# 1-Schematic_barbot_version1.net
KiCad netlist of a schematic drawn in EasyEDA
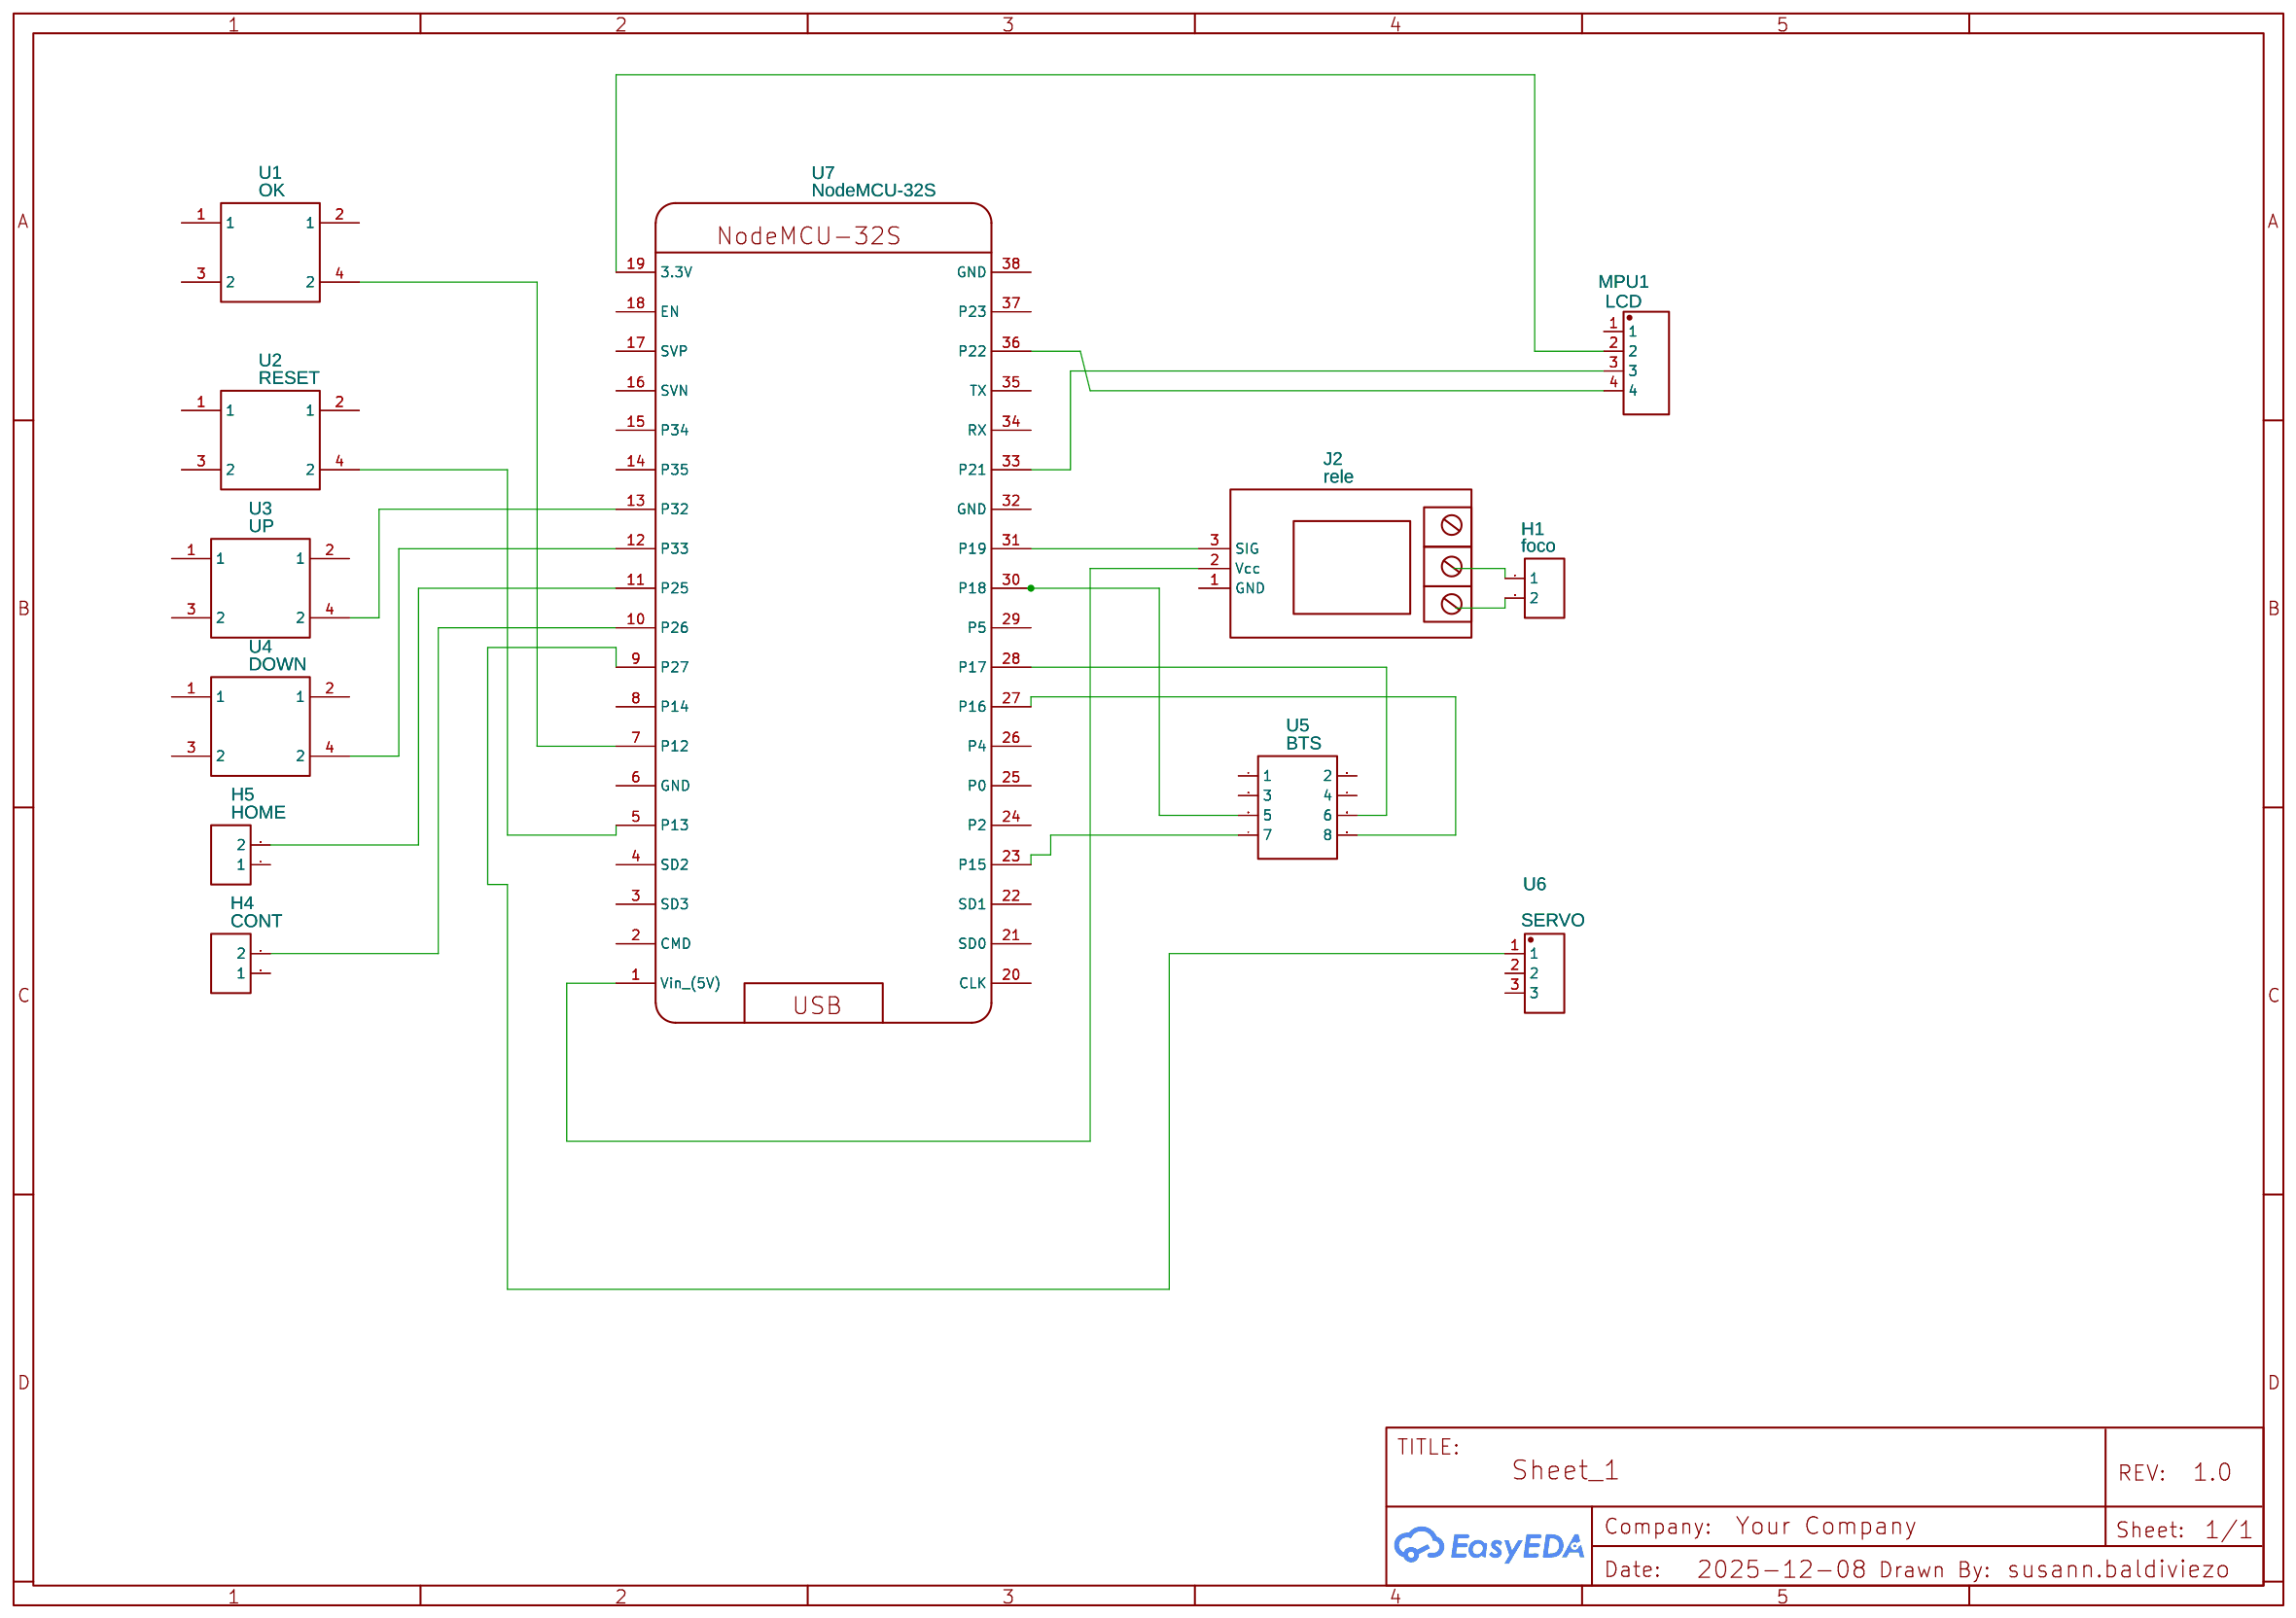
[diagram p0: schematic sheet]

(export (version "E")
  (design (tool "Eeschema 10.0.6"))
  (components
    (comp (ref "H1") (value "foco") (libsource (lib "") (part "HEADER-FEMALE-2.54_1X2 COPY")))
    (comp (ref "H4") (value "CONT") (libsource (lib "") (part "HEADER-FEMALE-2.54_1X2 COPY_1")))
    (comp (ref "H5") (value "HOME") (libsource (lib "") (part "HEADER-FEMALE-2.54_1X2 COPY_1")))
    (comp (ref "J2")
      (value "rele")
      (fields (field (name "Manufacturer Part") "1-Channel 5V Relay Module w/ Opto-isolator"))
      (libsource (lib "") (part "1 CHANNEL RELAY MODULE"))
    )
    (comp (ref "MPU1") (value "LCD") (libsource (lib "") (part "HEADER-FEMALE-2.54_1X4")))
    (comp (ref "U1") (value "OK") (libsource (lib "") (part "Boton pulsador 12x12mm")))
    (comp (ref "U2") (value "RESET") (libsource (lib "") (part "Boton pulsador 12x12mm")))
    (comp (ref "U3") (value "UP") (libsource (lib "") (part "Boton pulsador 12x12mm")))
    (comp (ref "U4") (value "DOWN") (libsource (lib "") (part "Boton pulsador 12x12mm")))
    (comp (ref "U5")
      (value "BTS")
      (fields (field (name "Manufacturer Part") "2.54mm,2×4Double row female"))
      (libsource (lib "") (part "Header-Female-2.54_2x10"))
    )
    (comp (ref "U6") (value "SERVO") (libsource (lib "") (part "HEADER-FEMALE-2.54_1X3")))
    (comp (ref "U7")
      (value "NodeMCU-32S")
      (fields (field (name "Manufacturer Part") "NodeMCU-32SLua") (field (name "Manufacturer") "Ai-Thinker"))
      (libsource (lib "") (part "NodeMCU-32S"))
    )
  )
  (nets
    (net (code "1") (name "Net-(J2-SIG)") (class "Default")
      (node (ref "J2") (pin "3") (pinfunction "SIG_3") (pintype "input"))
      (node (ref "U7") (pin "31") (pinfunction "P19_31") (pintype "unspecified"))
    )
    (net (code "2") (name "Net-(J2-Vcc)") (class "Default")
      (node (ref "J2") (pin "2") (pinfunction "Vcc_2") (pintype "input"))
      (node (ref "U7") (pin "1") (pinfunction "Vin_(5V)_1") (pintype "unspecified"))
    )
    (net (code "3") (name "Net-(U7-3.3V)") (class "Default")
      (node (ref "MPU1") (pin "2") (pinfunction "2_2") (pintype "unspecified"))
      (node (ref "U7") (pin "19") (pinfunction "3.3V_19") (pintype "unspecified"))
    )
    (net (code "4") (name "Net-(U7-P12)") (class "Default")
      (node (ref "U1") (pin "4") (pinfunction "2_4") (pintype "unspecified"))
      (node (ref "U7") (pin "7") (pinfunction "P12_7") (pintype "unspecified"))
    )
    (net (code "5") (name "Net-(U7-P13)") (class "Default")
      (node (ref "U2") (pin "4") (pinfunction "2_4") (pintype "unspecified"))
      (node (ref "U7") (pin "5") (pinfunction "P13_5") (pintype "unspecified"))
    )
    (net (code "6") (name "Net-(U7-P15)") (class "Default")
      (node (ref "U5") (pin "7") (pinfunction "7_7") (pintype "unspecified"))
      (node (ref "U7") (pin "23") (pinfunction "P15_23") (pintype "unspecified"))
    )
    (net (code "7") (name "Net-(U7-P16)") (class "Default")
      (node (ref "U5") (pin "8") (pinfunction "8_8") (pintype "unspecified"))
      (node (ref "U7") (pin "27") (pinfunction "P16_27") (pintype "unspecified"))
    )
    (net (code "8") (name "Net-(U7-P17)") (class "Default")
      (node (ref "U5") (pin "6") (pinfunction "6_6") (pintype "unspecified"))
      (node (ref "U7") (pin "28") (pinfunction "P17_28") (pintype "unspecified"))
    )
    (net (code "9") (name "Net-(U7-P18)") (class "Default")
      (node (ref "U5") (pin "5") (pinfunction "5_5") (pintype "unspecified"))
      (node (ref "U7") (pin "30") (pinfunction "P18_30") (pintype "unspecified"))
    )
    (net (code "10") (name "Net-(U7-P21)") (class "Default")
      (node (ref "MPU1") (pin "3") (pinfunction "3_3") (pintype "unspecified"))
      (node (ref "U7") (pin "33") (pinfunction "P21_33") (pintype "unspecified"))
    )
    (net (code "11") (name "Net-(U7-P22)") (class "Default")
      (node (ref "MPU1") (pin "4") (pinfunction "4_4") (pintype "unspecified"))
      (node (ref "U7") (pin "36") (pinfunction "P22_36") (pintype "unspecified"))
    )
    (net (code "12") (name "Net-(U7-P25)") (class "Default")
      (node (ref "H5") (pin "2") (pinfunction "2_2") (pintype "input"))
      (node (ref "U7") (pin "11") (pinfunction "P25_11") (pintype "unspecified"))
    )
    (net (code "13") (name "Net-(U7-P26)") (class "Default")
      (node (ref "H4") (pin "2") (pinfunction "2_2") (pintype "input"))
      (node (ref "U7") (pin "10") (pinfunction "P26_10") (pintype "unspecified"))
    )
    (net (code "14") (name "Net-(U7-P27)") (class "Default")
      (node (ref "U6") (pin "1") (pinfunction "1_1") (pintype "unspecified"))
      (node (ref "U7") (pin "9") (pinfunction "P27_9") (pintype "unspecified"))
    )
    (net (code "15") (name "Net-(U7-P32)") (class "Default")
      (node (ref "U3") (pin "4") (pinfunction "2_4") (pintype "unspecified"))
      (node (ref "U7") (pin "13") (pinfunction "P32_13") (pintype "unspecified"))
    )
    (net (code "16") (name "Net-(U7-P33)") (class "Default")
      (node (ref "U4") (pin "4") (pinfunction "2_4") (pintype "unspecified"))
      (node (ref "U7") (pin "12") (pinfunction "P33_12") (pintype "unspecified"))
    )
    (net (code "17") (name "unconnected-(H1-Pad1)") (class "Default")
      (node (ref "H1") (pin "1") (pinfunction "1_1") (pintype "input"))
    )
    (net (code "18") (name "unconnected-(H1-Pad2)") (class "Default")
      (node (ref "H1") (pin "2") (pinfunction "2_2") (pintype "input"))
    )
    (net (code "19") (name "unconnected-(H4-Pad1)") (class "Default")
      (node (ref "H4") (pin "1") (pinfunction "1_1") (pintype "input"))
    )
    (net (code "20") (name "unconnected-(H5-Pad1)") (class "Default")
      (node (ref "H5") (pin "1") (pinfunction "1_1") (pintype "input"))
    )
    (net (code "21") (name "unconnected-(J2-GND-Pad1)") (class "Default")
      (node (ref "J2") (pin "1") (pinfunction "GND_1") (pintype "input"))
    )
    (net (code "22") (name "unconnected-(MPU1-Pad1)") (class "Default")
      (node (ref "MPU1") (pin "1") (pinfunction "1_1") (pintype "unspecified"))
    )
    (net (code "23") (name "unconnected-(U1-1-Pad2)") (class "Default")
      (node (ref "U1") (pin "2") (pinfunction "1_2") (pintype "unspecified"))
    )
    (net (code "24") (name "unconnected-(U1-2-Pad3)") (class "Default")
      (node (ref "U1") (pin "3") (pinfunction "2_3") (pintype "unspecified"))
    )
    (net (code "25") (name "unconnected-(U1-Pad1)") (class "Default")
      (node (ref "U1") (pin "1") (pinfunction "1_1") (pintype "unspecified"))
    )
    (net (code "26") (name "unconnected-(U2-1-Pad2)") (class "Default")
      (node (ref "U2") (pin "2") (pinfunction "1_2") (pintype "unspecified"))
    )
    (net (code "27") (name "unconnected-(U2-2-Pad3)") (class "Default")
      (node (ref "U2") (pin "3") (pinfunction "2_3") (pintype "unspecified"))
    )
    (net (code "28") (name "unconnected-(U2-Pad1)") (class "Default")
      (node (ref "U2") (pin "1") (pinfunction "1_1") (pintype "unspecified"))
    )
    (net (code "29") (name "unconnected-(U3-1-Pad2)") (class "Default")
      (node (ref "U3") (pin "2") (pinfunction "1_2") (pintype "unspecified"))
    )
    (net (code "30") (name "unconnected-(U3-2-Pad3)") (class "Default")
      (node (ref "U3") (pin "3") (pinfunction "2_3") (pintype "unspecified"))
    )
    (net (code "31") (name "unconnected-(U3-Pad1)") (class "Default")
      (node (ref "U3") (pin "1") (pinfunction "1_1") (pintype "unspecified"))
    )
    (net (code "32") (name "unconnected-(U4-1-Pad2)") (class "Default")
      (node (ref "U4") (pin "2") (pinfunction "1_2") (pintype "unspecified"))
    )
    (net (code "33") (name "unconnected-(U4-2-Pad3)") (class "Default")
      (node (ref "U4") (pin "3") (pinfunction "2_3") (pintype "unspecified"))
    )
    (net (code "34") (name "unconnected-(U4-Pad1)") (class "Default")
      (node (ref "U4") (pin "1") (pinfunction "1_1") (pintype "unspecified"))
    )
    (net (code "35") (name "unconnected-(U5-Pad1)") (class "Default")
      (node (ref "U5") (pin "1") (pinfunction "1_1") (pintype "unspecified"))
    )
    (net (code "36") (name "unconnected-(U5-Pad2)") (class "Default")
      (node (ref "U5") (pin "2") (pinfunction "2_2") (pintype "unspecified"))
    )
    (net (code "37") (name "unconnected-(U5-Pad3)") (class "Default")
      (node (ref "U5") (pin "3") (pinfunction "3_3") (pintype "unspecified"))
    )
    (net (code "38") (name "unconnected-(U5-Pad4)") (class "Default")
      (node (ref "U5") (pin "4") (pinfunction "4_4") (pintype "unspecified"))
    )
    (net (code "39") (name "unconnected-(U6-Pad2)") (class "Default")
      (node (ref "U6") (pin "2") (pinfunction "2_2") (pintype "unspecified"))
    )
    (net (code "40") (name "unconnected-(U6-Pad3)") (class "Default")
      (node (ref "U6") (pin "3") (pinfunction "3_3") (pintype "unspecified"))
    )
    (net (code "41") (name "unconnected-(U7-CLK-Pad20)") (class "Default")
      (node (ref "U7") (pin "20") (pinfunction "CLK_20") (pintype "unspecified"))
    )
    (net (code "42") (name "unconnected-(U7-CMD-Pad2)") (class "Default")
      (node (ref "U7") (pin "2") (pinfunction "CMD_2") (pintype "unspecified"))
    )
    (net (code "43") (name "unconnected-(U7-EN-Pad18)") (class "Default")
      (node (ref "U7") (pin "18") (pinfunction "EN_18") (pintype "unspecified"))
    )
    (net (code "44") (name "unconnected-(U7-GND-Pad6)") (class "Default")
      (node (ref "U7") (pin "6") (pinfunction "GND_6") (pintype "unspecified"))
    )
    (net (code "45") (name "unconnected-(U7-GND-Pad32)") (class "Default")
      (node (ref "U7") (pin "32") (pinfunction "GND_32") (pintype "unspecified"))
    )
    (net (code "46") (name "unconnected-(U7-GND-Pad38)") (class "Default")
      (node (ref "U7") (pin "38") (pinfunction "GND_38") (pintype "unspecified"))
    )
    (net (code "47") (name "unconnected-(U7-P0-Pad25)") (class "Default")
      (node (ref "U7") (pin "25") (pinfunction "P0_25") (pintype "unspecified"))
    )
    (net (code "48") (name "unconnected-(U7-P2-Pad24)") (class "Default")
      (node (ref "U7") (pin "24") (pinfunction "P2_24") (pintype "unspecified"))
    )
    (net (code "49") (name "unconnected-(U7-P4-Pad26)") (class "Default")
      (node (ref "U7") (pin "26") (pinfunction "P4_26") (pintype "unspecified"))
    )
    (net (code "50") (name "unconnected-(U7-P5-Pad29)") (class "Default")
      (node (ref "U7") (pin "29") (pinfunction "P5_29") (pintype "unspecified"))
    )
    (net (code "51") (name "unconnected-(U7-P14-Pad8)") (class "Default")
      (node (ref "U7") (pin "8") (pinfunction "P14_8") (pintype "unspecified"))
    )
    (net (code "52") (name "unconnected-(U7-P23-Pad37)") (class "Default")
      (node (ref "U7") (pin "37") (pinfunction "P23_37") (pintype "unspecified"))
    )
    (net (code "53") (name "unconnected-(U7-P34-Pad15)") (class "Default")
      (node (ref "U7") (pin "15") (pinfunction "P34_15") (pintype "unspecified"))
    )
    (net (code "54") (name "unconnected-(U7-P35-Pad14)") (class "Default")
      (node (ref "U7") (pin "14") (pinfunction "P35_14") (pintype "unspecified"))
    )
    (net (code "55") (name "unconnected-(U7-RX-Pad34)") (class "Default")
      (node (ref "U7") (pin "34") (pinfunction "RX_34") (pintype "unspecified"))
    )
    (net (code "56") (name "unconnected-(U7-SD0-Pad21)") (class "Default")
      (node (ref "U7") (pin "21") (pinfunction "SD0_21") (pintype "unspecified"))
    )
    (net (code "57") (name "unconnected-(U7-SD1-Pad22)") (class "Default")
      (node (ref "U7") (pin "22") (pinfunction "SD1_22") (pintype "unspecified"))
    )
    (net (code "58") (name "unconnected-(U7-SD2-Pad4)") (class "Default")
      (node (ref "U7") (pin "4") (pinfunction "SD2_4") (pintype "unspecified"))
    )
    (net (code "59") (name "unconnected-(U7-SD3-Pad3)") (class "Default")
      (node (ref "U7") (pin "3") (pinfunction "SD3_3") (pintype "unspecified"))
    )
    (net (code "60") (name "unconnected-(U7-SVN-Pad16)") (class "Default")
      (node (ref "U7") (pin "16") (pinfunction "SVN_16") (pintype "unspecified"))
    )
    (net (code "61") (name "unconnected-(U7-SVP-Pad17)") (class "Default")
      (node (ref "U7") (pin "17") (pinfunction "SVP_17") (pintype "unspecified"))
    )
    (net (code "62") (name "unconnected-(U7-TX-Pad35)") (class "Default")
      (node (ref "U7") (pin "35") (pinfunction "TX_35") (pintype "unspecified"))
    )
  )
)
